# OpenBook_v17.net
KiCad netlist of a schematic drawn in EAGLE
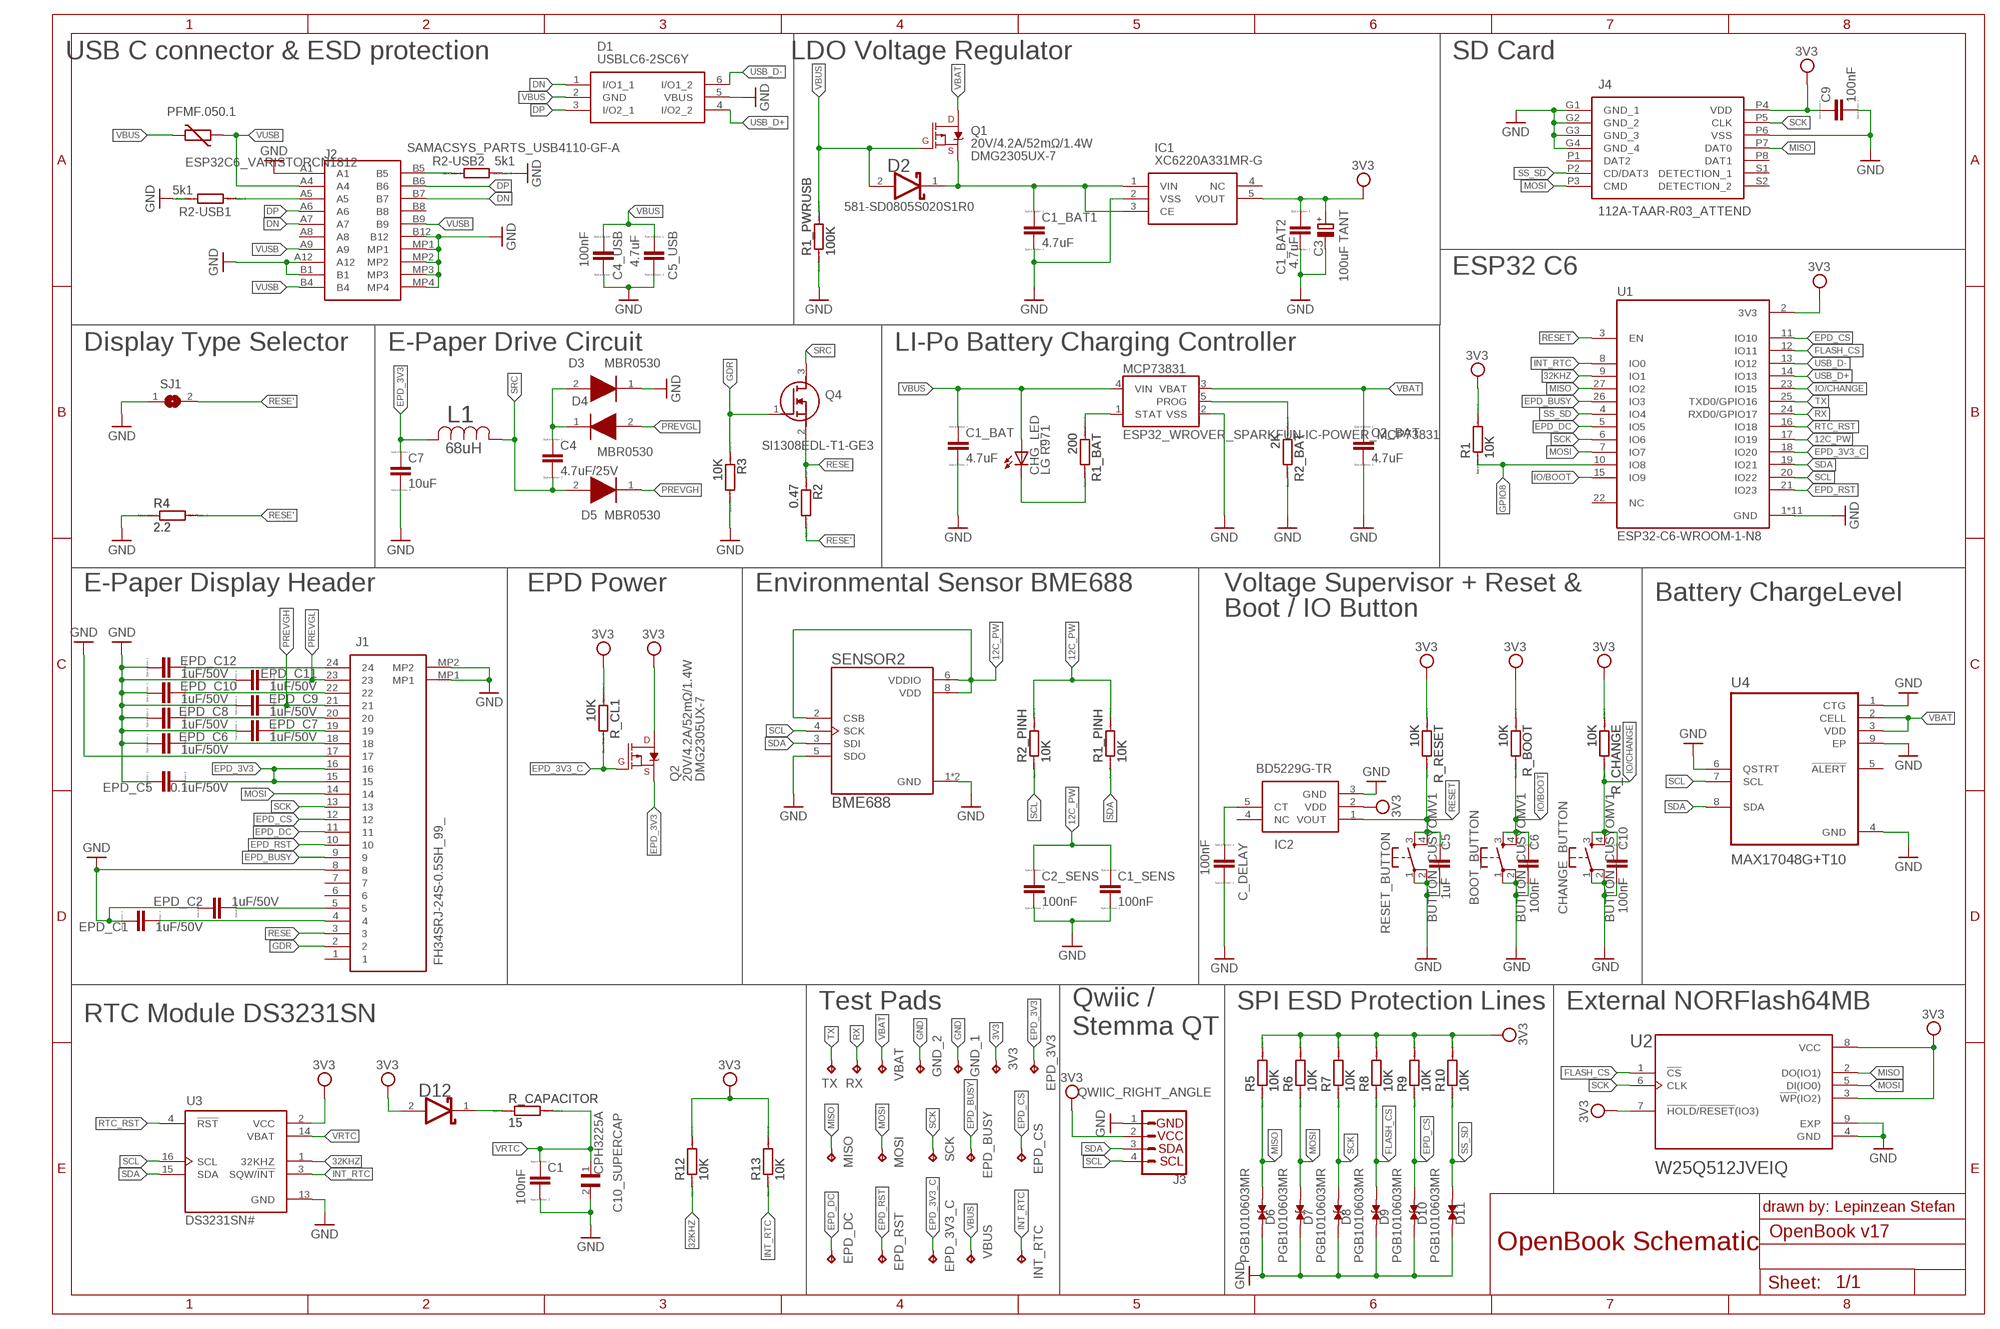
[diagram p0: schematic, sheet 1]

(export (version "E")
  (design (tool "Eeschema 10.0.6"))
  (components
    (comp (ref "3V3")
      (value "TPTP20R")
      (footprint "eagle-import:TP20R")
      (libsource (lib "eagle-import") (part "TPTP20R"))
    )
    (comp (ref "BOOT_BUTTON")
      (value "BUTTON_CUSYOMV1")
      (footprint "eagle-import:MYBUTTON")
      (libsource (lib "eagle-import") (part "BUTTON_CUSYOMV1"))
    )
    (comp (ref "C1")
      (value "100nF")
      (footprint "eagle-import:EAGLE-LTSPICE_C0402")
      (libsource (lib "eagle-import") (part "EAGLE-LTSPICE_CC0402"))
    )
    (comp (ref "C1_BAT")
      (value "4.7uF")
      (footprint "eagle-import:EAGLE-LTSPICE_C0402")
      (libsource (lib "eagle-import") (part "EAGLE-LTSPICE_CC0402"))
    )
    (comp (ref "C1_BAT1")
      (value "4.7uF")
      (footprint "eagle-import:EAGLE-LTSPICE_C0402")
      (libsource (lib "eagle-import") (part "EAGLE-LTSPICE_CC0402"))
    )
    (comp (ref "C1_BAT2")
      (value "4.7uF")
      (footprint "eagle-import:EAGLE-LTSPICE_C0402")
      (libsource (lib "eagle-import") (part "EAGLE-LTSPICE_CC0402"))
    )
    (comp (ref "C1_SENS")
      (value "100nF")
      (footprint "eagle-import:EAGLE-LTSPICE_C0402")
      (libsource (lib "eagle-import") (part "EAGLE-LTSPICE_CC0402"))
    )
    (comp (ref "C2_BAT")
      (value "4.7uF")
      (footprint "eagle-import:EAGLE-LTSPICE_C0402")
      (libsource (lib "eagle-import") (part "EAGLE-LTSPICE_CC0402"))
    )
    (comp (ref "C2_SENS")
      (value "100nF")
      (footprint "eagle-import:EAGLE-LTSPICE_C0402")
      (libsource (lib "eagle-import") (part "EAGLE-LTSPICE_CC0402"))
    )
    (comp (ref "C3")
      (value "100uF TANT")
      (footprint "eagle-import:RCL_CT3528")
      (libsource (lib "eagle-import") (part "RCL_CPOL-EUCT3528"))
    )
    (comp (ref "C4")
      (value "4.7uF/25V")
      (footprint "eagle-import:EAGLE-LTSPICE_C0402")
      (libsource (lib "eagle-import") (part "EAGLE-LTSPICE_CC0402"))
    )
    (comp (ref "C4_USB")
      (value "100nF")
      (footprint "eagle-import:EAGLE-LTSPICE_C0402")
      (libsource (lib "eagle-import") (part "EAGLE-LTSPICE_CC0402"))
    )
    (comp (ref "C5")
      (value "1uF")
      (footprint "eagle-import:EAGLE-LTSPICE_C0402")
      (libsource (lib "eagle-import") (part "EAGLE-LTSPICE_CC0402"))
    )
    (comp (ref "C5_USB")
      (value "4.7uF")
      (footprint "eagle-import:EAGLE-LTSPICE_C0402")
      (libsource (lib "eagle-import") (part "EAGLE-LTSPICE_CC0402"))
    )
    (comp (ref "C6")
      (value "100nF")
      (footprint "eagle-import:EAGLE-LTSPICE_C0402")
      (libsource (lib "eagle-import") (part "EAGLE-LTSPICE_CC0402"))
    )
    (comp (ref "C7")
      (value "10uF")
      (footprint "eagle-import:EAGLE-LTSPICE_C0402")
      (libsource (lib "eagle-import") (part "EAGLE-LTSPICE_CC0402"))
    )
    (comp (ref "C9")
      (value "100nF")
      (footprint "eagle-import:EAGLE-LTSPICE_C0402")
      (libsource (lib "eagle-import") (part "EAGLE-LTSPICE_CC0402"))
    )
    (comp (ref "C10")
      (value "100nF")
      (footprint "eagle-import:EAGLE-LTSPICE_C0402")
      (libsource (lib "eagle-import") (part "EAGLE-LTSPICE_CC0402"))
    )
    (comp (ref "C10_SUPERCAP")
      (value "CPH3225A")
      (footprint "eagle-import:CAPCP3225X100N")
      (fields (field (name "MF") "Seiko Instruments"))
      (libsource (lib "eagle-import") (part "CPH3225A"))
    )
    (comp (ref "CHANGE_BUTTON")
      (value "BUTTON_CUSYOMV1")
      (footprint "eagle-import:MYBUTTON")
      (libsource (lib "eagle-import") (part "BUTTON_CUSYOMV1"))
    )
    (comp (ref "CHG_LED")
      (value "LG R971")
      (footprint "eagle-import:ADAFRUIT_CHIP-LED0603")
      (libsource (lib "eagle-import") (part "ADAFRUIT_LEDCHIP-LED0603"))
    )
    (comp (ref "C_DELAY")
      (value "100nF")
      (footprint "eagle-import:EAGLE-LTSPICE_C0402")
      (libsource (lib "eagle-import") (part "EAGLE-LTSPICE_CC0402"))
    )
    (comp (ref "D1")
      (value "USBLC6-2SC6Y")
      (footprint "eagle-import:SOT95P280X145-6N")
      (fields (field (name "MF") "STMicroelectronics"))
      (libsource (lib "eagle-import") (part "USBLC6-2SC6Y"))
    )
    (comp (ref "D2")
      (value "ESP32_WROVER_AVX---SD0805S020S1R0_AVX_SD0805S020S1R0_0_0AVX_SD0805S020S1R0_0_0")
      (footprint "eagle-import:ESP32_WROVER_AVX---SD0805S020S1R0_AVX_SD0805S020S1R0_0")
      (fields
        (field (name "DIGIKEY_PART_NUMBER") "478-7800-1-ND")
        (field (name "MF") "AVX")
        (field (name "MOUSER_PART_NUMBER") "581-SD0805S020S1R0")
      )
      (libsource (lib "eagle-import") (part "ESP32_WROVER_AVX---SD0805S020S1R0_AVX_SD0805S020S1R0_0_0AVX_SD0805S020S1R0_0_0"))
    )
    (comp (ref "D3")
      (value "MBR0530")
      (footprint "eagle-import:SOD3716X135N")
      (fields (field (name "MF") "ON Semiconductor"))
      (libsource (lib "eagle-import") (part "MBR0530"))
    )
    (comp (ref "D4")
      (value "MBR0530")
      (footprint "eagle-import:SOD3716X135N")
      (fields (field (name "MF") "ON Semiconductor"))
      (libsource (lib "eagle-import") (part "MBR0530"))
    )
    (comp (ref "D5")
      (value "MBR0530")
      (footprint "eagle-import:SOD3716X135N")
      (fields (field (name "MF") "ON Semiconductor"))
      (libsource (lib "eagle-import") (part "MBR0530"))
    )
    (comp (ref "D6")
      (value "PGB1010603MR")
      (footprint "eagle-import:DIOC1608X36N")
      (fields (field (name "MF") "Littelfuse Inc."))
      (libsource (lib "eagle-import") (part "PGB1010603MR"))
    )
    (comp (ref "D7")
      (value "PGB1010603MR")
      (footprint "eagle-import:DIOC1608X36N")
      (fields (field (name "MF") "Littelfuse Inc."))
      (libsource (lib "eagle-import") (part "PGB1010603MR"))
    )
    (comp (ref "D8")
      (value "PGB1010603MR")
      (footprint "eagle-import:DIOC1608X36N")
      (fields (field (name "MF") "Littelfuse Inc."))
      (libsource (lib "eagle-import") (part "PGB1010603MR"))
    )
    (comp (ref "D9")
      (value "PGB1010603MR")
      (footprint "eagle-import:DIOC1608X36N")
      (fields (field (name "MF") "Littelfuse Inc."))
      (libsource (lib "eagle-import") (part "PGB1010603MR"))
    )
    (comp (ref "D10")
      (value "PGB1010603MR")
      (footprint "eagle-import:DIOC1608X36N")
      (fields (field (name "MF") "Littelfuse Inc."))
      (libsource (lib "eagle-import") (part "PGB1010603MR"))
    )
    (comp (ref "D11")
      (value "PGB1010603MR")
      (footprint "eagle-import:DIOC1608X36N")
      (fields (field (name "MF") "Littelfuse Inc."))
      (libsource (lib "eagle-import") (part "PGB1010603MR"))
    )
    (comp (ref "D12")
      (value "ESP32_WROVER_AVX---SD0805S020S1R0_AVX_SD0805S020S1R0_0_0AVX_SD0805S020S1R0_0_0")
      (footprint "eagle-import:ESP32_WROVER_AVX---SD0805S020S1R0_AVX_SD0805S020S1R0_0")
      (fields
        (field (name "DIGIKEY_PART_NUMBER") "478-7800-1-ND")
        (field (name "MF") "AVX")
        (field (name "MOUSER_PART_NUMBER") "581-SD0805S020S1R0")
      )
      (libsource (lib "eagle-import") (part "ESP32_WROVER_AVX---SD0805S020S1R0_AVX_SD0805S020S1R0_0_0AVX_SD0805S020S1R0_0_0"))
    )
    (comp (ref "EPD_3V3")
      (value "TPTP20R")
      (footprint "eagle-import:TP20R")
      (libsource (lib "eagle-import") (part "TPTP20R"))
    )
    (comp (ref "EPD_3V3_C")
      (value "TPTP20R")
      (footprint "eagle-import:TP20R")
      (libsource (lib "eagle-import") (part "TPTP20R"))
    )
    (comp (ref "EPD_BUSY")
      (value "TPTP20R")
      (footprint "eagle-import:TP20R")
      (libsource (lib "eagle-import") (part "TPTP20R"))
    )
    (comp (ref "EPD_C1")
      (value "1uF/50V")
      (footprint "eagle-import:EAGLE-LTSPICE_C0402")
      (libsource (lib "eagle-import") (part "EAGLE-LTSPICE_CC0402"))
    )
    (comp (ref "EPD_C2")
      (value "1uF/50V")
      (footprint "eagle-import:EAGLE-LTSPICE_C0402")
      (libsource (lib "eagle-import") (part "EAGLE-LTSPICE_CC0402"))
    )
    (comp (ref "EPD_C5")
      (value "0.1uF/50V")
      (footprint "eagle-import:EAGLE-LTSPICE_C0402")
      (libsource (lib "eagle-import") (part "EAGLE-LTSPICE_CC0402"))
    )
    (comp (ref "EPD_C6")
      (value "1uF/50V")
      (footprint "eagle-import:EAGLE-LTSPICE_C0402")
      (libsource (lib "eagle-import") (part "EAGLE-LTSPICE_CC0402"))
    )
    (comp (ref "EPD_C7")
      (value "1uF/50V")
      (footprint "eagle-import:EAGLE-LTSPICE_C0402")
      (libsource (lib "eagle-import") (part "EAGLE-LTSPICE_CC0402"))
    )
    (comp (ref "EPD_C8")
      (value "1uF/50V")
      (footprint "eagle-import:EAGLE-LTSPICE_C0402")
      (libsource (lib "eagle-import") (part "EAGLE-LTSPICE_CC0402"))
    )
    (comp (ref "EPD_C9")
      (value "1uF/50V")
      (footprint "eagle-import:EAGLE-LTSPICE_C0402")
      (libsource (lib "eagle-import") (part "EAGLE-LTSPICE_CC0402"))
    )
    (comp (ref "EPD_C10")
      (value "1uF/50V")
      (footprint "eagle-import:EAGLE-LTSPICE_C0402")
      (libsource (lib "eagle-import") (part "EAGLE-LTSPICE_CC0402"))
    )
    (comp (ref "EPD_C11")
      (value "1uF/50V")
      (footprint "eagle-import:EAGLE-LTSPICE_C0402")
      (libsource (lib "eagle-import") (part "EAGLE-LTSPICE_CC0402"))
    )
    (comp (ref "EPD_C12")
      (value "1uF/50V")
      (footprint "eagle-import:EAGLE-LTSPICE_C0402")
      (libsource (lib "eagle-import") (part "EAGLE-LTSPICE_CC0402"))
    )
    (comp (ref "EPD_CS")
      (value "TPTP20R")
      (footprint "eagle-import:TP20R")
      (libsource (lib "eagle-import") (part "TPTP20R"))
    )
    (comp (ref "EPD_DC")
      (value "TPTP20R")
      (footprint "eagle-import:TP20R")
      (libsource (lib "eagle-import") (part "TPTP20R"))
    )
    (comp (ref "EPD_RST")
      (value "TPTP20R")
      (footprint "eagle-import:TP20R")
      (libsource (lib "eagle-import") (part "TPTP20R"))
    )
    (comp (ref "GND_1")
      (value "TPTP20R")
      (footprint "eagle-import:TP20R")
      (libsource (lib "eagle-import") (part "TPTP20R"))
    )
    (comp (ref "GND_2")
      (value "TPTP20R")
      (footprint "eagle-import:TP20R")
      (libsource (lib "eagle-import") (part "TPTP20R"))
    )
    (comp (ref "IC1")
      (value "XC6220A331MR-G")
      (footprint "eagle-import:SOT95P280X120-5N")
      (fields (field (name "MOUSER_PART_NUMBER") "865-XC6220A331MR-G"))
      (libsource (lib "eagle-import") (part "XC6220A331MR-G"))
    )
    (comp (ref "IC2")
      (value "BD5229G-TR")
      (footprint "eagle-import:SOT95P280X125-5N")
      (fields (field (name "MOUSER_PART_NUMBER") "755-BD5229G-TR"))
      (libsource (lib "eagle-import") (part "BD5229G-TR"))
    )
    (comp (ref "INT_RTC")
      (value "TPTP20R")
      (footprint "eagle-import:TP20R")
      (libsource (lib "eagle-import") (part "TPTP20R"))
    )
    (comp (ref "J1")
      (value "FH34SRJ-24S-0.5SH_99_")
      (footprint "eagle-import:FH34SRJ24S05SH99")
      (fields
        (field (name "MANUFACTURER_PART_NUMBER") "FH34SRJ-24S-0.5SH(99)")
        (field (name "MOUSER_PART_NUMBER") "798-FH34SRJ24S05SH99")
      )
      (libsource (lib "eagle-import") (part "FH34SRJ-24S-0.5SH_99_"))
    )
    (comp (ref "J2")
      (value "SAMACSYS_PARTS_USB4110-GF-A")
      (footprint "eagle-import:SAMACSYS_PARTS_USB4110GFA")
      (fields
        (field (name "MANUFACTURER_PART_NUMBER") "USB4110-GF-A")
        (field (name "MOUSER_PART_NUMBER") "640-USB4110-GF-A")
      )
      (libsource (lib "eagle-import") (part "SAMACSYS_PARTS_USB4110-GF-A"))
    )
    (comp (ref "J3")
      (value "QWIIC_RIGHT_ANGLE")
      (footprint "eagle-import:JST04_1MM_RA")
      (libsource (lib "eagle-import") (part "QWIIC_CONNECTORJS-1MM"))
    )
    (comp (ref "J4")
      (value "112A-TAAR-R03_ATTEND")
      (footprint "eagle-import:112ATAARR03ATTEND")
      (fields (field (name "MANUFACTURER_PART_NUMBER") "112A-TAAR-R03 ATTEND"))
      (libsource (lib "eagle-import") (part "112A-TAAR-R03_ATTEND"))
    )
    (comp (ref "L1")
      (value "68uH")
      (footprint "eagle-import:IND_4828-WE-TPC_WRE")
      (fields
        (field (name "MANUFACTURER_PART_NUMBER") "744043680")
        (field (name "COPYRIGHT") "Copyright (C) 2024 Ultra Librarian. All rights reserved.")
      )
      (libsource (lib "eagle-import") (part "744043680IND_4828-WE-TPC_WRE"))
    )
    (comp (ref "MCP73831")
      (value "ESP32_WROVER_SPARKFUN-IC-POWER_MCP73831")
      (footprint "eagle-import:ESP32_WROVER_SPARKFUN-IC-POWER_SOT23-5")
      (libsource (lib "eagle-import") (part "ESP32_WROVER_SPARKFUN-IC-POWER_MCP73831"))
    )
    (comp (ref "MISO")
      (value "TPTP20R")
      (footprint "eagle-import:TP20R")
      (libsource (lib "eagle-import") (part "TPTP20R"))
    )
    (comp (ref "MOSI")
      (value "TPTP20R")
      (footprint "eagle-import:TP20R")
      (libsource (lib "eagle-import") (part "TPTP20R"))
    )
    (comp (ref "PFMF.050.1")
      (value "ESP32C6_VARISTORCN1812")
      (footprint "eagle-import:ESP32C6_VARISTOR_CT_CN1812")
      (libsource (lib "eagle-import") (part "ESP32C6_VARISTORCN1812"))
    )
    (comp (ref "Q1")
      (value "20V/4.2A/52mΩ/1.4W")
      (footprint "eagle-import:ESP32_WROVER_SPARKFUN-DISCRETESEMI_SOT23-3")
      (fields (field (name "PROD_ID") "DMG2305UX-7"))
      (libsource (lib "eagle-import") (part "ESP32_WROVER_SPARKFUN-DISCRETESEMI_MOSFET_PCH-DMG2305UX-7"))
    )
    (comp (ref "Q2")
      (value "20V/4.2A/52mΩ/1.4W")
      (footprint "eagle-import:ESP32_WROVER_SPARKFUN-DISCRETESEMI_SOT23-3")
      (fields (field (name "PROD_ID") "DMG2305UX-7"))
      (libsource (lib "eagle-import") (part "ESP32_WROVER_SPARKFUN-DISCRETESEMI_MOSFET_PCH-DMG2305UX-7"))
    )
    (comp (ref "Q4")
      (value "SI1308EDL-T1-GE3")
      (footprint "eagle-import:SOT65P210X110-3N")
      (fields (field (name "MF") "Vishay Siliconix"))
      (libsource (lib "eagle-import") (part "SI1308EDL-T1-GE3"))
    )
    (comp (ref "R1")
      (value "10K")
      (footprint "eagle-import:R0402")
      (libsource (lib "eagle-import") (part "ESP32_WROVER_EAGLE-LTSPICE_RR0402"))
    )
    (comp (ref "R1_BAT")
      (value "200")
      (footprint "eagle-import:R0402")
      (libsource (lib "eagle-import") (part "ESP32_WROVER_EAGLE-LTSPICE_RR0402"))
    )
    (comp (ref "R1_PINH")
      (value "10K")
      (footprint "eagle-import:R0402")
      (libsource (lib "eagle-import") (part "ESP32_WROVER_EAGLE-LTSPICE_RR0402"))
    )
    (comp (ref "R1_PWRUSB")
      (value "100K")
      (footprint "eagle-import:R0402")
      (libsource (lib "eagle-import") (part "ESP32_WROVER_EAGLE-LTSPICE_RR0402"))
    )
    (comp (ref "R2")
      (value "0.47")
      (footprint "eagle-import:R0402")
      (libsource (lib "eagle-import") (part "ESP32_WROVER_EAGLE-LTSPICE_RR0402"))
    )
    (comp (ref "R2-USB1")
      (value "5k1")
      (footprint "eagle-import:R0402")
      (libsource (lib "eagle-import") (part "ESP32_WROVER_EAGLE-LTSPICE_RR0402"))
    )
    (comp (ref "R2-USB2")
      (value "5k1")
      (footprint "eagle-import:R0402")
      (libsource (lib "eagle-import") (part "ESP32_WROVER_EAGLE-LTSPICE_RR0402"))
    )
    (comp (ref "R2_BAT")
      (value "2K")
      (footprint "eagle-import:R0402")
      (libsource (lib "eagle-import") (part "ESP32_WROVER_EAGLE-LTSPICE_RR0402"))
    )
    (comp (ref "R2_PINH")
      (value "10K")
      (footprint "eagle-import:R0402")
      (libsource (lib "eagle-import") (part "ESP32_WROVER_EAGLE-LTSPICE_RR0402"))
    )
    (comp (ref "R3")
      (value "10K")
      (footprint "eagle-import:R0402")
      (libsource (lib "eagle-import") (part "ESP32_WROVER_EAGLE-LTSPICE_RR0402"))
    )
    (comp (ref "R4")
      (value "2.2")
      (footprint "eagle-import:R0402")
      (libsource (lib "eagle-import") (part "ESP32_WROVER_EAGLE-LTSPICE_RR0402"))
    )
    (comp (ref "R5")
      (value "10K")
      (footprint "eagle-import:R0402")
      (libsource (lib "eagle-import") (part "ESP32_WROVER_EAGLE-LTSPICE_RR0402"))
    )
    (comp (ref "R6")
      (value "10K")
      (footprint "eagle-import:R0402")
      (libsource (lib "eagle-import") (part "ESP32_WROVER_EAGLE-LTSPICE_RR0402"))
    )
    (comp (ref "R7")
      (value "10K")
      (footprint "eagle-import:R0402")
      (libsource (lib "eagle-import") (part "ESP32_WROVER_EAGLE-LTSPICE_RR0402"))
    )
    (comp (ref "R8")
      (value "10K")
      (footprint "eagle-import:R0402")
      (libsource (lib "eagle-import") (part "ESP32_WROVER_EAGLE-LTSPICE_RR0402"))
    )
    (comp (ref "R9")
      (value "10K")
      (footprint "eagle-import:R0402")
      (libsource (lib "eagle-import") (part "ESP32_WROVER_EAGLE-LTSPICE_RR0402"))
    )
    (comp (ref "R10")
      (value "10K")
      (footprint "eagle-import:R0402")
      (libsource (lib "eagle-import") (part "ESP32_WROVER_EAGLE-LTSPICE_RR0402"))
    )
    (comp (ref "R12")
      (value "10K")
      (footprint "eagle-import:R0402")
      (libsource (lib "eagle-import") (part "ESP32_WROVER_EAGLE-LTSPICE_RR0402"))
    )
    (comp (ref "R13")
      (value "10K")
      (footprint "eagle-import:R0402")
      (libsource (lib "eagle-import") (part "ESP32_WROVER_EAGLE-LTSPICE_RR0402"))
    )
    (comp (ref "RESET_BUTTON")
      (value "BUTTON_CUSYOMV1")
      (footprint "eagle-import:MYBUTTON")
      (libsource (lib "eagle-import") (part "BUTTON_CUSYOMV1"))
    )
    (comp (ref "RX")
      (value "TPTP20R")
      (footprint "eagle-import:TP20R")
      (libsource (lib "eagle-import") (part "TPTP20R"))
    )
    (comp (ref "R_BOOT")
      (value "10K")
      (footprint "eagle-import:R0402")
      (libsource (lib "eagle-import") (part "ESP32_WROVER_EAGLE-LTSPICE_RR0402"))
    )
    (comp (ref "R_CAPACITOR")
      (value "15")
      (footprint "eagle-import:R0402")
      (libsource (lib "eagle-import") (part "ESP32_WROVER_EAGLE-LTSPICE_RR0402"))
    )
    (comp (ref "R_CHANGE")
      (value "10K")
      (footprint "eagle-import:R0402")
      (libsource (lib "eagle-import") (part "ESP32_WROVER_EAGLE-LTSPICE_RR0402"))
    )
    (comp (ref "R_CL1")
      (value "10K")
      (footprint "eagle-import:R0402")
      (libsource (lib "eagle-import") (part "ESP32_WROVER_EAGLE-LTSPICE_RR0402"))
    )
    (comp (ref "R_RESET")
      (value "10K")
      (footprint "eagle-import:R0402")
      (libsource (lib "eagle-import") (part "ESP32_WROVER_EAGLE-LTSPICE_RR0402"))
    )
    (comp (ref "SCK")
      (value "TPTP20R")
      (footprint "eagle-import:TP20R")
      (libsource (lib "eagle-import") (part "TPTP20R"))
    )
    (comp (ref "SENSOR2")
      (value "BME688")
      (footprint "eagle-import:ESP32_WROVER_BME680_PSON80P300X300X100-8N")
      (fields (field (name "MF") "Bosch Sensortec") (field (name "MP") "BME680"))
      (libsource (lib "eagle-import") (part "ESP32_WROVER_BME680_BME680"))
    )
    (comp (ref "SJ1") (value "SJ") (footprint "eagle-import:SJ") (libsource (lib "eagle-import") (part "SJ")))
    (comp (ref "TX")
      (value "TPTP20R")
      (footprint "eagle-import:TP20R")
      (libsource (lib "eagle-import") (part "TPTP20R"))
    )
    (comp (ref "U1")
      (value "ESP32-C6-WROOM-1-N8")
      (footprint "eagle-import:XCVR_ESP32-C6-WROOM-1-N8")
      (fields (field (name "MF") "Espressif Systems"))
      (libsource (lib "eagle-import") (part "ESP32-C6-WROOM-1-N8"))
    )
    (comp (ref "U2")
      (value "W25Q512JVEIQ")
      (footprint "eagle-import:SON127P600X800X80-9N")
      (fields (field (name "MF") "Winbond Electronics"))
      (libsource (lib "eagle-import") (part "W25Q512JVEIQ"))
    )
    (comp (ref "U3")
      (value "DS3231SN#")
      (footprint "eagle-import:SOIC127P1032X265-16N")
      (fields (field (name "MF") "Analog Devices"))
      (libsource (lib "eagle-import") (part "DS3231SN#"))
    )
    (comp (ref "U4")
      (value "MAX17048G+T10")
      (footprint "eagle-import:SON50P200X200X80-9N")
      (fields (field (name "MF") "Analog Devices"))
      (libsource (lib "eagle-import") (part "MAX17048G+T10"))
    )
    (comp (ref "VBAT")
      (value "TPTP20R")
      (footprint "eagle-import:TP20R")
      (libsource (lib "eagle-import") (part "TPTP20R"))
    )
    (comp (ref "VBUS")
      (value "TPTP20R")
      (footprint "eagle-import:TP20R")
      (libsource (lib "eagle-import") (part "TPTP20R"))
    )
  )
  (nets
    (net (code "1") (name "3V3") (class "Default")
      (node (ref "3V3") (pin "TP") (pinfunction "TP_TP") (pintype "input"))
      (node (ref "C1_BAT2") (pin "2") (pinfunction "2_2") (pintype "passive"))
      (node (ref "C3") (pin "+") (pinfunction "+_+") (pintype "passive"))
      (node (ref "C9") (pin "1") (pinfunction "1_1") (pintype "passive"))
      (node (ref "D12") (pin "2") (pinfunction "ANODE_2") (pintype "bidirectional"))
      (node (ref "IC1") (pin "5") (pinfunction "VOUT_5") (pintype "bidirectional"))
      (node (ref "IC2") (pin "2") (pinfunction "VDD_2") (pintype "bidirectional"))
      (node (ref "J3") (pin "2") (pinfunction "2_2") (pintype "power_in"))
      (node (ref "J4") (pin "P4") (pinfunction "VDD_P4") (pintype "bidirectional"))
      (node (ref "Q2") (pin "3") (pinfunction "D_3") (pintype "bidirectional"))
      (node (ref "R1") (pin "2") (pinfunction "2_2") (pintype "passive"))
      (node (ref "R10") (pin "2") (pinfunction "2_2") (pintype "passive"))
      (node (ref "R12") (pin "2") (pinfunction "2_2") (pintype "passive"))
      (node (ref "R13") (pin "2") (pinfunction "2_2") (pintype "passive"))
      (node (ref "R5") (pin "2") (pinfunction "2_2") (pintype "passive"))
      (node (ref "R6") (pin "2") (pinfunction "2_2") (pintype "passive"))
      (node (ref "R7") (pin "2") (pinfunction "2_2") (pintype "passive"))
      (node (ref "R8") (pin "2") (pinfunction "2_2") (pintype "passive"))
      (node (ref "R9") (pin "2") (pinfunction "2_2") (pintype "passive"))
      (node (ref "R_BOOT") (pin "1") (pinfunction "1_1") (pintype "passive"))
      (node (ref "R_CHANGE") (pin "1") (pinfunction "1_1") (pintype "passive"))
      (node (ref "R_CL1") (pin "1") (pinfunction "1_1") (pintype "passive"))
      (node (ref "R_RESET") (pin "1") (pinfunction "1_1") (pintype "passive"))
      (node (ref "U1") (pin "2") (pinfunction "3V3_2") (pintype "power_in"))
      (node (ref "U2") (pin "3") (pinfunction "~{WP}(IO2)_3") (pintype "bidirectional"))
      (node (ref "U2") (pin "7") (pinfunction "~{HOLD}/~{RESET}(IO3)_7") (pintype "bidirectional"))
      (node (ref "U2") (pin "8") (pinfunction "VCC_8") (pintype "power_in"))
      (node (ref "U3") (pin "2") (pinfunction "VCC_2") (pintype "power_in"))
    )
    (net (code "2") (name "12C_PW") (class "Default")
      (node (ref "C1_SENS") (pin "1") (pinfunction "1_1") (pintype "passive"))
      (node (ref "C2_SENS") (pin "1") (pinfunction "1_1") (pintype "passive"))
      (node (ref "R1_PINH") (pin "2") (pinfunction "2_2") (pintype "passive"))
      (node (ref "R2_PINH") (pin "2") (pinfunction "2_2") (pintype "passive"))
      (node (ref "SENSOR2") (pin "2") (pinfunction "CSB_2") (pintype "input"))
      (node (ref "SENSOR2") (pin "6") (pinfunction "VDDIO_6") (pintype "power_in"))
      (node (ref "SENSOR2") (pin "8") (pinfunction "VDD_8") (pintype "power_in"))
      (node (ref "U1") (pin "17") (pinfunction "IO19_17") (pintype "bidirectional"))
    )
    (net (code "3") (name "32KHZ") (class "Default")
      (node (ref "R12") (pin "1") (pinfunction "1_1") (pintype "passive"))
      (node (ref "U1") (pin "9") (pinfunction "IO1_9") (pintype "bidirectional"))
      (node (ref "U3") (pin "1") (pinfunction "32KHZ_1") (pintype "output"))
    )
    (net (code "4") (name "DN") (class "Default")
      (node (ref "D1") (pin "1") (pinfunction "I/O1_1_1") (pintype "bidirectional"))
      (node (ref "J2") (pin "A7") (pinfunction "A7_A7") (pintype "bidirectional"))
      (node (ref "J2") (pin "B7") (pinfunction "B7_B7") (pintype "bidirectional"))
    )
    (net (code "5") (name "DP") (class "Default")
      (node (ref "D1") (pin "3") (pinfunction "I/O2_1_3") (pintype "bidirectional"))
      (node (ref "J2") (pin "A6") (pinfunction "A6_A6") (pintype "bidirectional"))
      (node (ref "J2") (pin "B6") (pinfunction "B6_B6") (pintype "bidirectional"))
    )
    (net (code "6") (name "EPD_3V3") (class "Default")
      (node (ref "C7") (pin "1") (pinfunction "1_1") (pintype "passive"))
      (node (ref "EPD_3V3") (pin "TP") (pinfunction "TP_TP") (pintype "input"))
      (node (ref "EPD_C5") (pin "2") (pinfunction "2_2") (pintype "passive"))
      (node (ref "J1") (pin "15") (pinfunction "15_15") (pintype "bidirectional"))
      (node (ref "J1") (pin "16") (pinfunction "16_16") (pintype "bidirectional"))
      (node (ref "L1") (pin "2") (pinfunction "2_2") (pintype "passive"))
      (node (ref "Q2") (pin "2") (pinfunction "S_2") (pintype "bidirectional"))
    )
    (net (code "7") (name "EPD_3V3_C") (class "Default")
      (node (ref "EPD_3V3_C") (pin "TP") (pinfunction "TP_TP") (pintype "input"))
      (node (ref "Q2") (pin "1") (pinfunction "G_1") (pintype "bidirectional"))
      (node (ref "R_CL1") (pin "2") (pinfunction "2_2") (pintype "passive"))
      (node (ref "U1") (pin "18") (pinfunction "IO20_18") (pintype "bidirectional"))
    )
    (net (code "8") (name "EPD_BUSY") (class "Default")
      (node (ref "EPD_BUSY") (pin "TP") (pinfunction "TP_TP") (pintype "input"))
      (node (ref "J1") (pin "9") (pinfunction "9_9") (pintype "bidirectional"))
      (node (ref "U1") (pin "26") (pinfunction "IO3_26") (pintype "bidirectional"))
    )
    (net (code "9") (name "EPD_CS") (class "Default")
      (node (ref "D10") (pin "2") (pinfunction "2_2") (pintype "passive"))
      (node (ref "EPD_CS") (pin "TP") (pinfunction "TP_TP") (pintype "input"))
      (node (ref "J1") (pin "12") (pinfunction "12_12") (pintype "bidirectional"))
      (node (ref "R9") (pin "1") (pinfunction "1_1") (pintype "passive"))
      (node (ref "U1") (pin "11") (pinfunction "IO10_11") (pintype "bidirectional"))
    )
    (net (code "10") (name "EPD_DC") (class "Default")
      (node (ref "EPD_DC") (pin "TP") (pinfunction "TP_TP") (pintype "input"))
      (node (ref "J1") (pin "11") (pinfunction "11_11") (pintype "bidirectional"))
      (node (ref "U1") (pin "5") (pinfunction "IO5_5") (pintype "bidirectional"))
    )
    (net (code "11") (name "EPD_RST") (class "Default")
      (node (ref "EPD_RST") (pin "TP") (pinfunction "TP_TP") (pintype "input"))
      (node (ref "J1") (pin "10") (pinfunction "10_10") (pintype "bidirectional"))
      (node (ref "U1") (pin "21") (pinfunction "IO23_21") (pintype "bidirectional"))
    )
    (net (code "12") (name "FLASH_CS") (class "Default")
      (node (ref "D9") (pin "2") (pinfunction "2_2") (pintype "passive"))
      (node (ref "R8") (pin "1") (pinfunction "1_1") (pintype "passive"))
      (node (ref "U1") (pin "12") (pinfunction "IO11_12") (pintype "bidirectional"))
      (node (ref "U2") (pin "1") (pinfunction "~{CS}_1") (pintype "input"))
    )
    (net (code "13") (name "GDR") (class "Default")
      (node (ref "J1") (pin "2") (pinfunction "2_2") (pintype "bidirectional"))
      (node (ref "Q4") (pin "1") (pinfunction "G_1") (pintype "bidirectional"))
      (node (ref "R3") (pin "1") (pinfunction "1_1") (pintype "passive"))
    )
    (net (code "14") (name "GND") (class "Default")
      (node (ref "BOOT_BUTTON") (pin "1") (pinfunction "1_1") (pintype "passive"))
      (node (ref "BOOT_BUTTON") (pin "2") (pinfunction "2_2") (pintype "passive"))
      (node (ref "C1") (pin "2") (pinfunction "2_2") (pintype "passive"))
      (node (ref "C10") (pin "2") (pinfunction "2_2") (pintype "passive"))
      (node (ref "C10_SUPERCAP") (pin "2") (pinfunction "2_2") (pintype "passive"))
      (node (ref "C1_BAT") (pin "2") (pinfunction "2_2") (pintype "passive"))
      (node (ref "C1_BAT1") (pin "2") (pinfunction "2_2") (pintype "passive"))
      (node (ref "C1_BAT2") (pin "1") (pinfunction "1_1") (pintype "passive"))
      (node (ref "C1_SENS") (pin "2") (pinfunction "2_2") (pintype "passive"))
      (node (ref "C2_BAT") (pin "2") (pinfunction "2_2") (pintype "passive"))
      (node (ref "C2_SENS") (pin "2") (pinfunction "2_2") (pintype "passive"))
      (node (ref "C3") (pin "-") (pinfunction "-_-") (pintype "passive"))
      (node (ref "C4_USB") (pin "2") (pinfunction "2_2") (pintype "passive"))
      (node (ref "C5") (pin "2") (pinfunction "2_2") (pintype "passive"))
      (node (ref "C5_USB") (pin "2") (pinfunction "2_2") (pintype "passive"))
      (node (ref "C6") (pin "2") (pinfunction "2_2") (pintype "passive"))
      (node (ref "C7") (pin "2") (pinfunction "2_2") (pintype "passive"))
      (node (ref "C9") (pin "2") (pinfunction "2_2") (pintype "passive"))
      (node (ref "CHANGE_BUTTON") (pin "1") (pinfunction "1_1") (pintype "passive"))
      (node (ref "CHANGE_BUTTON") (pin "2") (pinfunction "2_2") (pintype "passive"))
      (node (ref "C_DELAY") (pin "2") (pinfunction "2_2") (pintype "passive"))
      (node (ref "D1") (pin "5") (pinfunction "VBUS_5") (pintype "bidirectional"))
      (node (ref "D10") (pin "1") (pinfunction "1_1") (pintype "passive"))
      (node (ref "D11") (pin "1") (pinfunction "1_1") (pintype "passive"))
      (node (ref "D3") (pin "1") (pinfunction "K_1") (pintype "bidirectional"))
      (node (ref "D6") (pin "1") (pinfunction "1_1") (pintype "passive"))
      (node (ref "D7") (pin "1") (pinfunction "1_1") (pintype "passive"))
      (node (ref "D8") (pin "1") (pinfunction "1_1") (pintype "passive"))
      (node (ref "D9") (pin "1") (pinfunction "1_1") (pintype "passive"))
      (node (ref "EPD_C1") (pin "1") (pinfunction "1_1") (pintype "passive"))
      (node (ref "EPD_C10") (pin "1") (pinfunction "1_1") (pintype "passive"))
      (node (ref "EPD_C11") (pin "1") (pinfunction "1_1") (pintype "passive"))
      (node (ref "EPD_C12") (pin "1") (pinfunction "1_1") (pintype "passive"))
      (node (ref "EPD_C2") (pin "1") (pinfunction "1_1") (pintype "passive"))
      (node (ref "EPD_C5") (pin "1") (pinfunction "1_1") (pintype "passive"))
      (node (ref "EPD_C6") (pin "1") (pinfunction "1_1") (pintype "passive"))
      (node (ref "EPD_C7") (pin "1") (pinfunction "1_1") (pintype "passive"))
      (node (ref "EPD_C8") (pin "1") (pinfunction "1_1") (pintype "passive"))
      (node (ref "EPD_C9") (pin "1") (pinfunction "1_1") (pintype "passive"))
      (node (ref "GND_1") (pin "TP") (pinfunction "TP_TP") (pintype "input"))
      (node (ref "GND_2") (pin "TP") (pinfunction "TP_TP") (pintype "input"))
      (node (ref "IC1") (pin "2") (pinfunction "VSS_2") (pintype "bidirectional"))
      (node (ref "IC2") (pin "3") (pinfunction "GND_3") (pintype "bidirectional"))
      (node (ref "J1") (pin "17") (pinfunction "17_17") (pintype "bidirectional"))
      (node (ref "J1") (pin "8") (pinfunction "8_8") (pintype "bidirectional"))
      (node (ref "J1") (pin "MP1") (pinfunction "MP1_MP1") (pintype "bidirectional"))
      (node (ref "J1") (pin "MP2") (pinfunction "MP2_MP2") (pintype "bidirectional"))
      (node (ref "J2") (pin "A1") (pinfunction "A1_A1") (pintype "bidirectional"))
      (node (ref "J2") (pin "A12") (pinfunction "A12_A12") (pintype "bidirectional"))
      (node (ref "J2") (pin "B1") (pinfunction "B1_B1") (pintype "bidirectional"))
      (node (ref "J2") (pin "B12") (pinfunction "B12_B12") (pintype "bidirectional"))
      (node (ref "J2") (pin "MP1") (pinfunction "MP1_MP1") (pintype "bidirectional"))
      (node (ref "J2") (pin "MP2") (pinfunction "MP2_MP2") (pintype "bidirectional"))
      (node (ref "J2") (pin "MP3") (pinfunction "MP3_MP3") (pintype "bidirectional"))
      (node (ref "J2") (pin "MP4") (pinfunction "MP4_MP4") (pintype "bidirectional"))
      (node (ref "J3") (pin "1") (pinfunction "1_1") (pintype "power_in"))
      (node (ref "J4") (pin "G1") (pinfunction "GND_1_G1") (pintype "bidirectional"))
      (node (ref "J4") (pin "G2") (pinfunction "GND_2_G2") (pintype "bidirectional"))
      (node (ref "J4") (pin "G3") (pinfunction "GND_3_G3") (pintype "bidirectional"))
      (node (ref "J4") (pin "G4") (pinfunction "GND_4_G4") (pintype "bidirectional"))
      (node (ref "J4") (pin "P6") (pinfunction "VSS_P6") (pintype "bidirectional"))
      (node (ref "MCP73831") (pin "2") (pinfunction "VSS_2") (pintype "power_in"))
      (node (ref "R1_PWRUSB") (pin "1") (pinfunction "1_1") (pintype "passive"))
      (node (ref "R2-USB1") (pin "1") (pinfunction "1_1") (pintype "passive"))
      (node (ref "R2-USB2") (pin "2") (pinfunction "2_2") (pintype "passive"))
      (node (ref "R2_BAT") (pin "2") (pinfunction "2_2") (pintype "passive"))
      (node (ref "R3") (pin "2") (pinfunction "2_2") (pintype "passive"))
      (node (ref "R4") (pin "1") (pinfunction "1_1") (pintype "passive"))
      (node (ref "RESET_BUTTON") (pin "1") (pinfunction "1_1") (pintype "passive"))
      (node (ref "RESET_BUTTON") (pin "2") (pinfunction "2_2") (pintype "passive"))
      (node (ref "SENSOR2") (pin "1") (pinfunction "GND_1") (pintype "power_in"))
      (node (ref "SENSOR2") (pin "5") (pinfunction "SDO_5") (pintype "bidirectional"))
      (node (ref "SENSOR2") (pin "7") (pinfunction "GND_7") (pintype "power_in"))
      (node (ref "SJ1") (pin "1") (pinfunction "1_1") (pintype "passive"))
      (node (ref "U1") (pin "1") (pinfunction "GND_1") (pintype "power_in"))
      (node (ref "U1") (pin "28") (pinfunction "GND_28") (pintype "power_in"))
      (node (ref "U1") (pin "29_1") (pinfunction "GND_29_1") (pintype "power_in"))
      (node (ref "U1") (pin "29_2") (pinfunction "GND_29_2") (pintype "power_in"))
      (node (ref "U1") (pin "29_3") (pinfunction "GND_29_3") (pintype "power_in"))
      (node (ref "U1") (pin "29_4") (pinfunction "GND_29_4") (pintype "power_in"))
      (node (ref "U1") (pin "29_5") (pinfunction "GND_29_5") (pintype "power_in"))
      (node (ref "U1") (pin "29_6") (pinfunction "GND_29_6") (pintype "power_in"))
      (node (ref "U1") (pin "29_7") (pinfunction "GND_29_7") (pintype "power_in"))
      (node (ref "U1") (pin "29_8") (pinfunction "GND_29_8") (pintype "power_in"))
      (node (ref "U1") (pin "29_9") (pinfunction "GND_29_9") (pintype "power_in"))
      (node (ref "U2") (pin "4") (pinfunction "GND_4") (pintype "power_in"))
      (node (ref "U2") (pin "9") (pinfunction "EXP_9") (pintype "passive"))
      (node (ref "U3") (pin "13") (pinfunction "GND_13") (pintype "power_in"))
      (node (ref "U4") (pin "1") (pinfunction "CTG_1") (pintype "power_in"))
      (node (ref "U4") (pin "4") (pinfunction "GND_4") (pintype "power_in"))
      (node (ref "U4") (pin "6") (pinfunction "QSTRT_6") (pintype "input"))
      (node (ref "U4") (pin "9") (pinfunction "EP_9") (pintype "power_in"))
    )
    (net (code "15") (name "GPIO8") (class "Default")
      (node (ref "R1") (pin "1") (pinfunction "1_1") (pintype "passive"))
      (node (ref "U1") (pin "10") (pinfunction "IO8_10") (pintype "bidirectional"))
    )
    (net (code "16") (name "INT_RTC") (class "Default")
      (node (ref "INT_RTC") (pin "TP") (pinfunction "TP_TP") (pintype "input"))
      (node (ref "R13") (pin "1") (pinfunction "1_1") (pintype "passive"))
      (node (ref "U1") (pin "8") (pinfunction "IO0_8") (pintype "bidirectional"))
      (node (ref "U3") (pin "3") (pinfunction "SQW/~{INT}_3") (pintype "output"))
    )
    (net (code "17") (name "IO{slash}BOOT") (class "Default")
      (node (ref "BOOT_BUTTON") (pin "3") (pinfunction "3_3") (pintype "passive"))
      (node (ref "BOOT_BUTTON") (pin "4") (pinfunction "4_4") (pintype "passive"))
      (node (ref "C6") (pin "1") (pinfunction "1_1") (pintype "passive"))
      (node (ref "R_BOOT") (pin "2") (pinfunction "2_2") (pintype "passive"))
      (node (ref "U1") (pin "15") (pinfunction "IO9_15") (pintype "bidirectional"))
    )
    (net (code "18") (name "IO{slash}CHANGE") (class "Default")
      (node (ref "C10") (pin "1") (pinfunction "1_1") (pintype "passive"))
      (node (ref "CHANGE_BUTTON") (pin "3") (pinfunction "3_3") (pintype "passive"))
      (node (ref "CHANGE_BUTTON") (pin "4") (pinfunction "4_4") (pintype "passive"))
      (node (ref "R_CHANGE") (pin "2") (pinfunction "2_2") (pintype "passive"))
      (node (ref "U1") (pin "23") (pinfunction "IO15_23") (pintype "bidirectional"))
    )
    (net (code "19") (name "MISO") (class "Default")
      (node (ref "D6") (pin "2") (pinfunction "2_2") (pintype "passive"))
      (node (ref "J4") (pin "P7") (pinfunction "DAT0_P7") (pintype "bidirectional"))
      (node (ref "MISO") (pin "TP") (pinfunction "TP_TP") (pintype "input"))
      (node (ref "R5") (pin "1") (pinfunction "1_1") (pintype "passive"))
      (node (ref "U1") (pin "27") (pinfunction "IO2_27") (pintype "bidirectional"))
      (node (ref "U2") (pin "2") (pinfunction "DO(IO1)_2") (pintype "bidirectional"))
    )
    (net (code "20") (name "MOSI") (class "Default")
      (node (ref "D7") (pin "2") (pinfunction "2_2") (pintype "passive"))
      (node (ref "J1") (pin "14") (pinfunction "14_14") (pintype "bidirectional"))
      (node (ref "J4") (pin "P3") (pinfunction "CMD_P3") (pintype "bidirectional"))
      (node (ref "MOSI") (pin "TP") (pinfunction "TP_TP") (pintype "input"))
      (node (ref "R6") (pin "1") (pinfunction "1_1") (pintype "passive"))
      (node (ref "U1") (pin "7") (pinfunction "IO7_7") (pintype "bidirectional"))
      (node (ref "U2") (pin "5") (pinfunction "DI(IO0)_5") (pintype "bidirectional"))
    )
    (net (code "21") (name "Net-(CHG_LED-PadC)") (class "Default")
      (node (ref "CHG_LED") (pin "C") (pinfunction "C_C") (pintype "passive"))
      (node (ref "R1_BAT") (pin "2") (pinfunction "2_2") (pintype "passive"))
    )
    (net (code "22") (name "Net-(D2-CATHODE)") (class "Default")
      (node (ref "C1_BAT1") (pin "1") (pinfunction "1_1") (pintype "passive"))
      (node (ref "D2") (pin "1") (pinfunction "CATHODE_1") (pintype "bidirectional"))
      (node (ref "IC1") (pin "1") (pinfunction "VIN_1") (pintype "bidirectional"))
      (node (ref "IC1") (pin "3") (pinfunction "CE_3") (pintype "bidirectional"))
      (node (ref "Q1") (pin "2") (pinfunction "S_2") (pintype "bidirectional"))
    )
    (net (code "23") (name "Net-(D3-A)") (class "Default")
      (node (ref "C4") (pin "1") (pinfunction "1_1") (pintype "passive"))
      (node (ref "D3") (pin "2") (pinfunction "A_2") (pintype "bidirectional"))
      (node (ref "D4") (pin "1") (pinfunction "K_1") (pintype "bidirectional"))
    )
    (net (code "24") (name "Net-(D12-CATHODE)") (class "Default")
      (node (ref "D12") (pin "1") (pinfunction "CATHODE_1") (pintype "bidirectional"))
      (node (ref "R_CAPACITOR") (pin "1") (pinfunction "1_1") (pintype "passive"))
    )
    (net (code "25") (name "Net-(EPD_C1-Pad2)") (class "Default")
      (node (ref "EPD_C1") (pin "2") (pinfunction "2_2") (pintype "passive"))
      (node (ref "J1") (pin "4") (pinfunction "4_4") (pintype "bidirectional"))
    )
    (net (code "26") (name "Net-(EPD_C2-Pad2)") (class "Default")
      (node (ref "EPD_C2") (pin "2") (pinfunction "2_2") (pintype "passive"))
      (node (ref "J1") (pin "5") (pinfunction "5_5") (pintype "bidirectional"))
    )
    (net (code "27") (name "Net-(EPD_C6-Pad2)") (class "Default")
      (node (ref "EPD_C6") (pin "2") (pinfunction "2_2") (pintype "passive"))
      (node (ref "J1") (pin "18") (pinfunction "18_18") (pintype "bidirectional"))
    )
    (net (code "28") (name "Net-(EPD_C7-Pad2)") (class "Default")
      (node (ref "EPD_C7") (pin "2") (pinfunction "2_2") (pintype "passive"))
      (node (ref "J1") (pin "19") (pinfunction "19_19") (pintype "bidirectional"))
    )
    (net (code "29") (name "Net-(EPD_C8-Pad2)") (class "Default")
      (node (ref "EPD_C8") (pin "2") (pinfunction "2_2") (pintype "passive"))
      (node (ref "J1") (pin "20") (pinfunction "20_20") (pintype "bidirectional"))
    )
    (net (code "30") (name "Net-(EPD_C10-Pad2)") (class "Default")
      (node (ref "EPD_C10") (pin "2") (pinfunction "2_2") (pintype "passive"))
      (node (ref "J1") (pin "22") (pinfunction "22_22") (pintype "bidirectional"))
    )
    (net (code "31") (name "Net-(EPD_C12-Pad2)") (class "Default")
      (node (ref "EPD_C12") (pin "2") (pinfunction "2_2") (pintype "passive"))
      (node (ref "J1") (pin "24") (pinfunction "24_24") (pintype "bidirectional"))
    )
    (net (code "32") (name "Net-(IC2-CT)") (class "Default")
      (node (ref "C_DELAY") (pin "1") (pinfunction "1_1") (pintype "passive"))
      (node (ref "IC2") (pin "5") (pinfunction "CT_5") (pintype "bidirectional"))
    )
    (net (code "33") (name "Net-(J2-PadA5)") (class "Default")
      (node (ref "J2") (pin "A5") (pinfunction "A5_A5") (pintype "bidirectional"))
      (node (ref "R2-USB1") (pin "2") (pinfunction "2_2") (pintype "passive"))
    )
    (net (code "34") (name "Net-(J2-PadB5)") (class "Default")
      (node (ref "J2") (pin "B5") (pinfunction "B5_B5") (pintype "bidirectional"))
      (node (ref "R2-USB2") (pin "1") (pinfunction "1_1") (pintype "passive"))
    )
    (net (code "35") (name "Net-(MCP73831-PROG)") (class "Default")
      (node (ref "MCP73831") (pin "5") (pinfunction "PROG_5") (pintype "input"))
      (node (ref "R2_BAT") (pin "1") (pinfunction "1_1") (pintype "passive"))
    )
    (net (code "36") (name "Net-(MCP73831-STAT)") (class "Default")
      (node (ref "MCP73831") (pin "1") (pinfunction "STAT_1") (pintype "output"))
      (node (ref "R1_BAT") (pin "1") (pinfunction "1_1") (pintype "passive"))
    )
    (net (code "37") (name "PREVGH") (class "Default")
      (node (ref "D5") (pin "1") (pinfunction "K_1") (pintype "bidirectional"))
      (node (ref "EPD_C9") (pin "2") (pinfunction "2_2") (pintype "passive"))
      (node (ref "J1") (pin "21") (pinfunction "21_21") (pintype "bidirectional"))
    )
    (net (code "38") (name "PREVGL") (class "Default")
      (node (ref "D4") (pin "2") (pinfunction "A_2") (pintype "bidirectional"))
      (node (ref "EPD_C11") (pin "2") (pinfunction "2_2") (pintype "passive"))
      (node (ref "J1") (pin "23") (pinfunction "23_23") (pintype "bidirectional"))
    )
    (net (code "39") (name "RESE") (class "Default")
      (node (ref "J1") (pin "3") (pinfunction "3_3") (pintype "bidirectional"))
      (node (ref "Q4") (pin "2") (pinfunction "S_2") (pintype "bidirectional"))
      (node (ref "R2") (pin "1") (pinfunction "1_1") (pintype "passive"))
    )
    (net (code "40") (name "RESE'") (class "Default")
      (node (ref "R2") (pin "2") (pinfunction "2_2") (pintype "passive"))
      (node (ref "R4") (pin "2") (pinfunction "2_2") (pintype "passive"))
      (node (ref "SJ1") (pin "2") (pinfunction "2_2") (pintype "passive"))
    )
    (net (code "41") (name "RESET") (class "Default")
      (node (ref "C5") (pin "1") (pinfunction "1_1") (pintype "passive"))
      (node (ref "IC2") (pin "1") (pinfunction "VOUT_1") (pintype "bidirectional"))
      (node (ref "RESET_BUTTON") (pin "3") (pinfunction "3_3") (pintype "passive"))
      (node (ref "RESET_BUTTON") (pin "4") (pinfunction "4_4") (pintype "passive"))
      (node (ref "R_RESET") (pin "2") (pinfunction "2_2") (pintype "passive"))
      (node (ref "U1") (pin "3") (pinfunction "EN_3") (pintype "input"))
    )
    (net (code "42") (name "RTC_RST") (class "Default")
      (node (ref "U1") (pin "16") (pinfunction "IO18_16") (pintype "bidirectional"))
      (node (ref "U3") (pin "4") (pinfunction "~{RST}_4") (pintype "input"))
    )
    (net (code "43") (name "RX") (class "Default")
      (node (ref "RX") (pin "TP") (pinfunction "TP_TP") (pintype "input"))
      (node (ref "U1") (pin "24") (pinfunction "RXD0/GPIO17_24") (pintype "bidirectional"))
    )
    (net (code "44") (name "SCK") (class "Default")
      (node (ref "D8") (pin "2") (pinfunction "2_2") (pintype "passive"))
      (node (ref "J1") (pin "13") (pinfunction "13_13") (pintype "bidirectional"))
      (node (ref "J4") (pin "P5") (pinfunction "CLK_P5") (pintype "bidirectional"))
      (node (ref "R7") (pin "1") (pinfunction "1_1") (pintype "passive"))
      (node (ref "SCK") (pin "TP") (pinfunction "TP_TP") (pintype "input"))
      (node (ref "U1") (pin "6") (pinfunction "IO6_6") (pintype "bidirectional"))
      (node (ref "U2") (pin "6") (pinfunction "CLK_6") (pintype "input"))
    )
    (net (code "45") (name "SCL") (class "Default")
      (node (ref "J3") (pin "4") (pinfunction "4_4") (pintype "passive"))
      (node (ref "R2_PINH") (pin "1") (pinfunction "1_1") (pintype "passive"))
      (node (ref "SENSOR2") (pin "4") (pinfunction "SCK_4") (pintype "input"))
      (node (ref "U1") (pin "20") (pinfunction "IO22_20") (pintype "bidirectional"))
      (node (ref "U3") (pin "16") (pinfunction "SCL_16") (pintype "input"))
      (node (ref "U4") (pin "7") (pinfunction "SCL_7") (pintype "input"))
    )
    (net (code "46") (name "SDA") (class "Default")
      (node (ref "J3") (pin "3") (pinfunction "3_3") (pintype "passive"))
      (node (ref "R1_PINH") (pin "1") (pinfunction "1_1") (pintype "passive"))
      (node (ref "SENSOR2") (pin "3") (pinfunction "SDI_3") (pintype "bidirectional"))
      (node (ref "U1") (pin "19") (pinfunction "IO21_19") (pintype "bidirectional"))
      (node (ref "U3") (pin "15") (pinfunction "SDA_15") (pintype "bidirectional"))
      (node (ref "U4") (pin "8") (pinfunction "SDA_8") (pintype "bidirectional"))
    )
    (net (code "47") (name "SRC") (class "Default")
      (node (ref "C4") (pin "2") (pinfunction "2_2") (pintype "passive"))
      (node (ref "D5") (pin "2") (pinfunction "A_2") (pintype "bidirectional"))
      (node (ref "L1") (pin "1") (pinfunction "1_1") (pintype "passive"))
      (node (ref "Q4") (pin "3") (pinfunction "D_3") (pintype "bidirectional"))
    )
    (net (code "48") (name "SS_SD") (class "Default")
      (node (ref "D11") (pin "2") (pinfunction "2_2") (pintype "passive"))
      (node (ref "J4") (pin "P2") (pinfunction "CD/DAT3_P2") (pintype "bidirectional"))
      (node (ref "R10") (pin "1") (pinfunction "1_1") (pintype "passive"))
      (node (ref "U1") (pin "4") (pinfunction "IO4_4") (pintype "bidirectional"))
    )
    (net (code "49") (name "TX") (class "Default")
      (node (ref "TX") (pin "TP") (pinfunction "TP_TP") (pintype "input"))
      (node (ref "U1") (pin "25") (pinfunction "TXD0/GPIO16_25") (pintype "bidirectional"))
    )
    (net (code "50") (name "USB_D+") (class "Default")
      (node (ref "D1") (pin "4") (pinfunction "I/O2_2_4") (pintype "bidirectional"))
      (node (ref "U1") (pin "14") (pinfunction "IO13_14") (pintype "bidirectional"))
    )
    (net (code "51") (name "USB_D-") (class "Default")
      (node (ref "D1") (pin "6") (pinfunction "I/O1_2_6") (pintype "bidirectional"))
      (node (ref "U1") (pin "13") (pinfunction "IO12_13") (pintype "bidirectional"))
    )
    (net (code "52") (name "VBAT") (class "Default")
      (node (ref "C2_BAT") (pin "1") (pinfunction "1_1") (pintype "passive"))
      (node (ref "MCP73831") (pin "3") (pinfunction "VBAT_3") (pintype "power_in"))
      (node (ref "Q1") (pin "3") (pinfunction "D_3") (pintype "bidirectional"))
      (node (ref "U4") (pin "2") (pinfunction "CELL_2") (pintype "power_in"))
      (node (ref "U4") (pin "3") (pinfunction "VDD_3") (pintype "power_in"))
      (node (ref "VBAT") (pin "TP") (pinfunction "TP_TP") (pintype "input"))
    )
    (net (code "53") (name "VBUS") (class "Default")
      (node (ref "C1_BAT") (pin "1") (pinfunction "1_1") (pintype "passive"))
      (node (ref "C4_USB") (pin "1") (pinfunction "1_1") (pintype "passive"))
      (node (ref "C5_USB") (pin "1") (pinfunction "1_1") (pintype "passive"))
      (node (ref "CHG_LED") (pin "A") (pinfunction "A_A") (pintype "passive"))
      (node (ref "D1") (pin "2") (pinfunction "GND_2") (pintype "bidirectional"))
      (node (ref "D2") (pin "2") (pinfunction "ANODE_2") (pintype "bidirectional"))
      (node (ref "MCP73831") (pin "4") (pinfunction "VIN_4") (pintype "power_in"))
      (node (ref "PFMF.050.1") (pin "2") (pinfunction "2_2") (pintype "passive"))
      (node (ref "Q1") (pin "1") (pinfunction "G_1") (pintype "bidirectional"))
      (node (ref "R1_PWRUSB") (pin "2") (pinfunction "2_2") (pintype "passive"))
      (node (ref "VBUS") (pin "TP") (pinfunction "TP_TP") (pintype "input"))
    )
    (net (code "54") (name "VRTC") (class "Default")
      (node (ref "C1") (pin "1") (pinfunction "1_1") (pintype "passive"))
      (node (ref "C10_SUPERCAP") (pin "1") (pinfunction "1_1") (pintype "passive"))
      (node (ref "R_CAPACITOR") (pin "2") (pinfunction "2_2") (pintype "passive"))
      (node (ref "U3") (pin "14") (pinfunction "VBAT_14") (pintype "power_in"))
    )
    (net (code "55") (name "VUSB") (class "Default")
      (node (ref "J2") (pin "A4") (pinfunction "A4_A4") (pintype "bidirectional"))
      (node (ref "J2") (pin "A9") (pinfunction "A9_A9") (pintype "bidirectional"))
      (node (ref "J2") (pin "B4") (pinfunction "B4_B4") (pintype "bidirectional"))
      (node (ref "J2") (pin "B9") (pinfunction "B9_B9") (pintype "bidirectional"))
      (node (ref "PFMF.050.1") (pin "1") (pinfunction "1_1") (pintype "passive"))
    )
    (net (code "56") (name "unconnected-(IC1-NC-Pad4)") (class "Default")
      (node (ref "IC1") (pin "4") (pinfunction "NC_4") (pintype "no_connect"))
    )
    (net (code "57") (name "unconnected-(IC2-NC-Pad4)") (class "Default")
      (node (ref "IC2") (pin "4") (pinfunction "NC_4") (pintype "no_connect"))
    )
    (net (code "58") (name "unconnected-(J1-Pad1)") (class "Default")
      (node (ref "J1") (pin "1") (pinfunction "1_1") (pintype "bidirectional"))
    )
    (net (code "59") (name "unconnected-(J1-Pad6)") (class "Default")
      (node (ref "J1") (pin "6") (pinfunction "6_6") (pintype "bidirectional"))
    )
    (net (code "60") (name "unconnected-(J1-Pad7)") (class "Default")
      (node (ref "J1") (pin "7") (pinfunction "7_7") (pintype "bidirectional"))
    )
    (net (code "61") (name "unconnected-(J2-PadA8)") (class "Default")
      (node (ref "J2") (pin "A8") (pinfunction "A8_A8") (pintype "bidirectional"))
    )
    (net (code "62") (name "unconnected-(J2-PadB8)") (class "Default")
      (node (ref "J2") (pin "B8") (pinfunction "B8_B8") (pintype "bidirectional"))
    )
    (net (code "63") (name "unconnected-(J4-DAT1-PadP8)") (class "Default")
      (node (ref "J4") (pin "P8") (pinfunction "DAT1_P8") (pintype "bidirectional"))
    )
    (net (code "64") (name "unconnected-(J4-DAT2-PadP1)") (class "Default")
      (node (ref "J4") (pin "P1") (pinfunction "DAT2_P1") (pintype "bidirectional"))
    )
    (net (code "65") (name "unconnected-(J4-DETECTION_1-PadS1)") (class "Default")
      (node (ref "J4") (pin "S1") (pinfunction "DETECTION_1_S1") (pintype "bidirectional"))
    )
    (net (code "66") (name "unconnected-(J4-DETECTION_2-PadS2)") (class "Default")
      (node (ref "J4") (pin "S2") (pinfunction "DETECTION_2_S2") (pintype "bidirectional"))
    )
    (net (code "67") (name "unconnected-(U1-NC-Pad22)") (class "Default")
      (node (ref "U1") (pin "22") (pinfunction "NC_22") (pintype "no_connect"))
    )
    (net (code "68") (name "unconnected-(U4-~{ALERT}-Pad5)") (class "Default")
      (node (ref "U4") (pin "5") (pinfunction "~{ALERT}_5") (pintype "output"))
    )
  )
)
